# Low-Frequency-LC-Oscillator.net
KiCad netlist of a schematic drawn in EAGLE
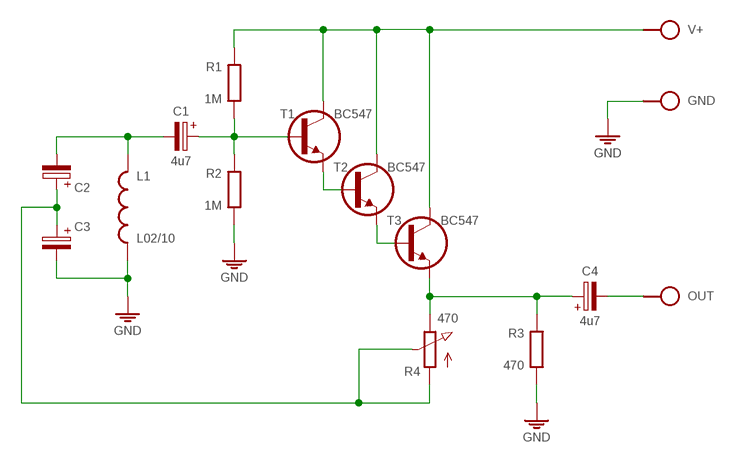
[diagram p0: schematic, sheet 1]

(export (version "E")
  (design (tool "Eeschema 10.0.6"))
  (components
    (comp (ref "C1")
      (value "4u7")
      (footprint "eagle-import:E2,5-3")
      (libsource (lib "eagle-import") (part "CPOLE2,5-3"))
    )
    (comp (ref "C2")
      (value "CPOLE2.5-5")
      (footprint "eagle-import:E2,5-5")
      (libsource (lib "eagle-import") (part "CPOLE2.5-5"))
    )
    (comp (ref "C3")
      (value "CPOLE2.5-5")
      (footprint "eagle-import:E2,5-5")
      (libsource (lib "eagle-import") (part "CPOLE2.5-5"))
    )
    (comp (ref "C4")
      (value "4u7")
      (footprint "eagle-import:E2,5-3")
      (libsource (lib "eagle-import") (part "CPOLE2,5-3"))
    )
    (comp (ref "GND")
      (value "SPAD")
      (footprint "eagle-import:SPAD")
      (libsource (lib "eagle-import") (part "SPAD"))
    )
    (comp (ref "L1")
      (value "L02/10")
      (footprint "eagle-import:L-03_10V")
      (libsource (lib "eagle-import") (part "L02/10"))
    )
    (comp (ref "OUT")
      (value "SPAD")
      (footprint "eagle-import:SPAD")
      (libsource (lib "eagle-import") (part "SPAD"))
    )
    (comp (ref "R1")
      (value "1M")
      (footprint "eagle-import:0204_10")
      (libsource (lib "eagle-import") (part "R0204/10"))
    )
    (comp (ref "R2")
      (value "1M")
      (footprint "eagle-import:0204_10")
      (libsource (lib "eagle-import") (part "R0204/10"))
    )
    (comp (ref "R3")
      (value "470")
      (footprint "eagle-import:0204_10")
      (libsource (lib "eagle-import") (part "R0204/10"))
    )
    (comp (ref "R4")
      (value "470")
      (footprint "eagle-import:POT")
      (libsource (lib "eagle-import") (part "POT"))
    )
    (comp (ref "T1")
      (value "BC547")
      (footprint "eagle-import:TO92-CBE")
      (libsource (lib "eagle-import") (part "BC547CBE"))
    )
    (comp (ref "T2")
      (value "BC547")
      (footprint "eagle-import:TO92-CBE")
      (libsource (lib "eagle-import") (part "BC547CBE"))
    )
    (comp (ref "T3")
      (value "BC547")
      (footprint "eagle-import:TO92-CBE")
      (libsource (lib "eagle-import") (part "BC547CBE"))
    )
    (comp (ref "V+")
      (value "SPAD")
      (footprint "eagle-import:SPAD")
      (libsource (lib "eagle-import") (part "SPAD"))
    )
  )
  (nets
    (net (code "1") (name "GND") (class "Default")
      (node (ref "C3") (pin "-") (pinfunction "-_-") (pintype "passive"))
      (node (ref "GND") (pin "1") (pinfunction "P$1_1") (pintype "bidirectional"))
      (node (ref "L1") (pin "2") (pinfunction "2_2") (pintype "passive"))
      (node (ref "R2") (pin "1") (pinfunction "1_1") (pintype "passive"))
      (node (ref "R3") (pin "1") (pinfunction "1_1") (pintype "passive"))
    )
    (net (code "2") (name "Net-(C1-Pad+)") (class "Default")
      (node (ref "C1") (pin "+") (pinfunction "+_+") (pintype "passive"))
      (node (ref "R1") (pin "1") (pinfunction "1_1") (pintype "passive"))
      (node (ref "R2") (pin "2") (pinfunction "2_2") (pintype "passive"))
      (node (ref "T1") (pin "B") (pinfunction "B_B") (pintype "passive"))
    )
    (net (code "3") (name "Net-(C1-Pad-)") (class "Default")
      (node (ref "C1") (pin "-") (pinfunction "-_-") (pintype "passive"))
      (node (ref "C2") (pin "-") (pinfunction "-_-") (pintype "passive"))
      (node (ref "L1") (pin "1") (pinfunction "1_1") (pintype "passive"))
    )
    (net (code "4") (name "Net-(OUT-P$1)") (class "Default")
      (node (ref "C4") (pin "-") (pinfunction "-_-") (pintype "passive"))
      (node (ref "OUT") (pin "1") (pinfunction "P$1_1") (pintype "bidirectional"))
    )
    (net (code "5") (name "Net-(R4-A)") (class "Default")
      (node (ref "C2") (pin "+") (pinfunction "+_+") (pintype "passive"))
      (node (ref "C3") (pin "+") (pinfunction "+_+") (pintype "passive"))
      (node (ref "R4") (pin "1") (pinfunction "A_1") (pintype "passive"))
      (node (ref "R4") (pin "2") (pinfunction "S_2") (pintype "passive"))
    )
    (net (code "6") (name "Net-(R4-E)") (class "Default")
      (node (ref "C4") (pin "+") (pinfunction "+_+") (pintype "passive"))
      (node (ref "R3") (pin "2") (pinfunction "2_2") (pintype "passive"))
      (node (ref "R4") (pin "3") (pinfunction "E_3") (pintype "passive"))
      (node (ref "T3") (pin "E") (pinfunction "E_E") (pintype "passive"))
    )
    (net (code "7") (name "Net-(T1-PadE)") (class "Default")
      (node (ref "T1") (pin "E") (pinfunction "E_E") (pintype "passive"))
      (node (ref "T2") (pin "B") (pinfunction "B_B") (pintype "passive"))
    )
    (net (code "8") (name "Net-(T2-PadE)") (class "Default")
      (node (ref "T2") (pin "E") (pinfunction "E_E") (pintype "passive"))
      (node (ref "T3") (pin "B") (pinfunction "B_B") (pintype "passive"))
    )
    (net (code "9") (name "Net-(V+-P$1)") (class "Default")
      (node (ref "R1") (pin "2") (pinfunction "2_2") (pintype "passive"))
      (node (ref "T1") (pin "C") (pinfunction "C_C") (pintype "passive"))
      (node (ref "T2") (pin "C") (pinfunction "C_C") (pintype "passive"))
      (node (ref "T3") (pin "C") (pinfunction "C_C") (pintype "passive"))
      (node (ref "V+") (pin "1") (pinfunction "P$1_1") (pintype "bidirectional"))
    )
  )
)
